# Rev_1.net
KiCad netlist of a schematic drawn in EAGLE
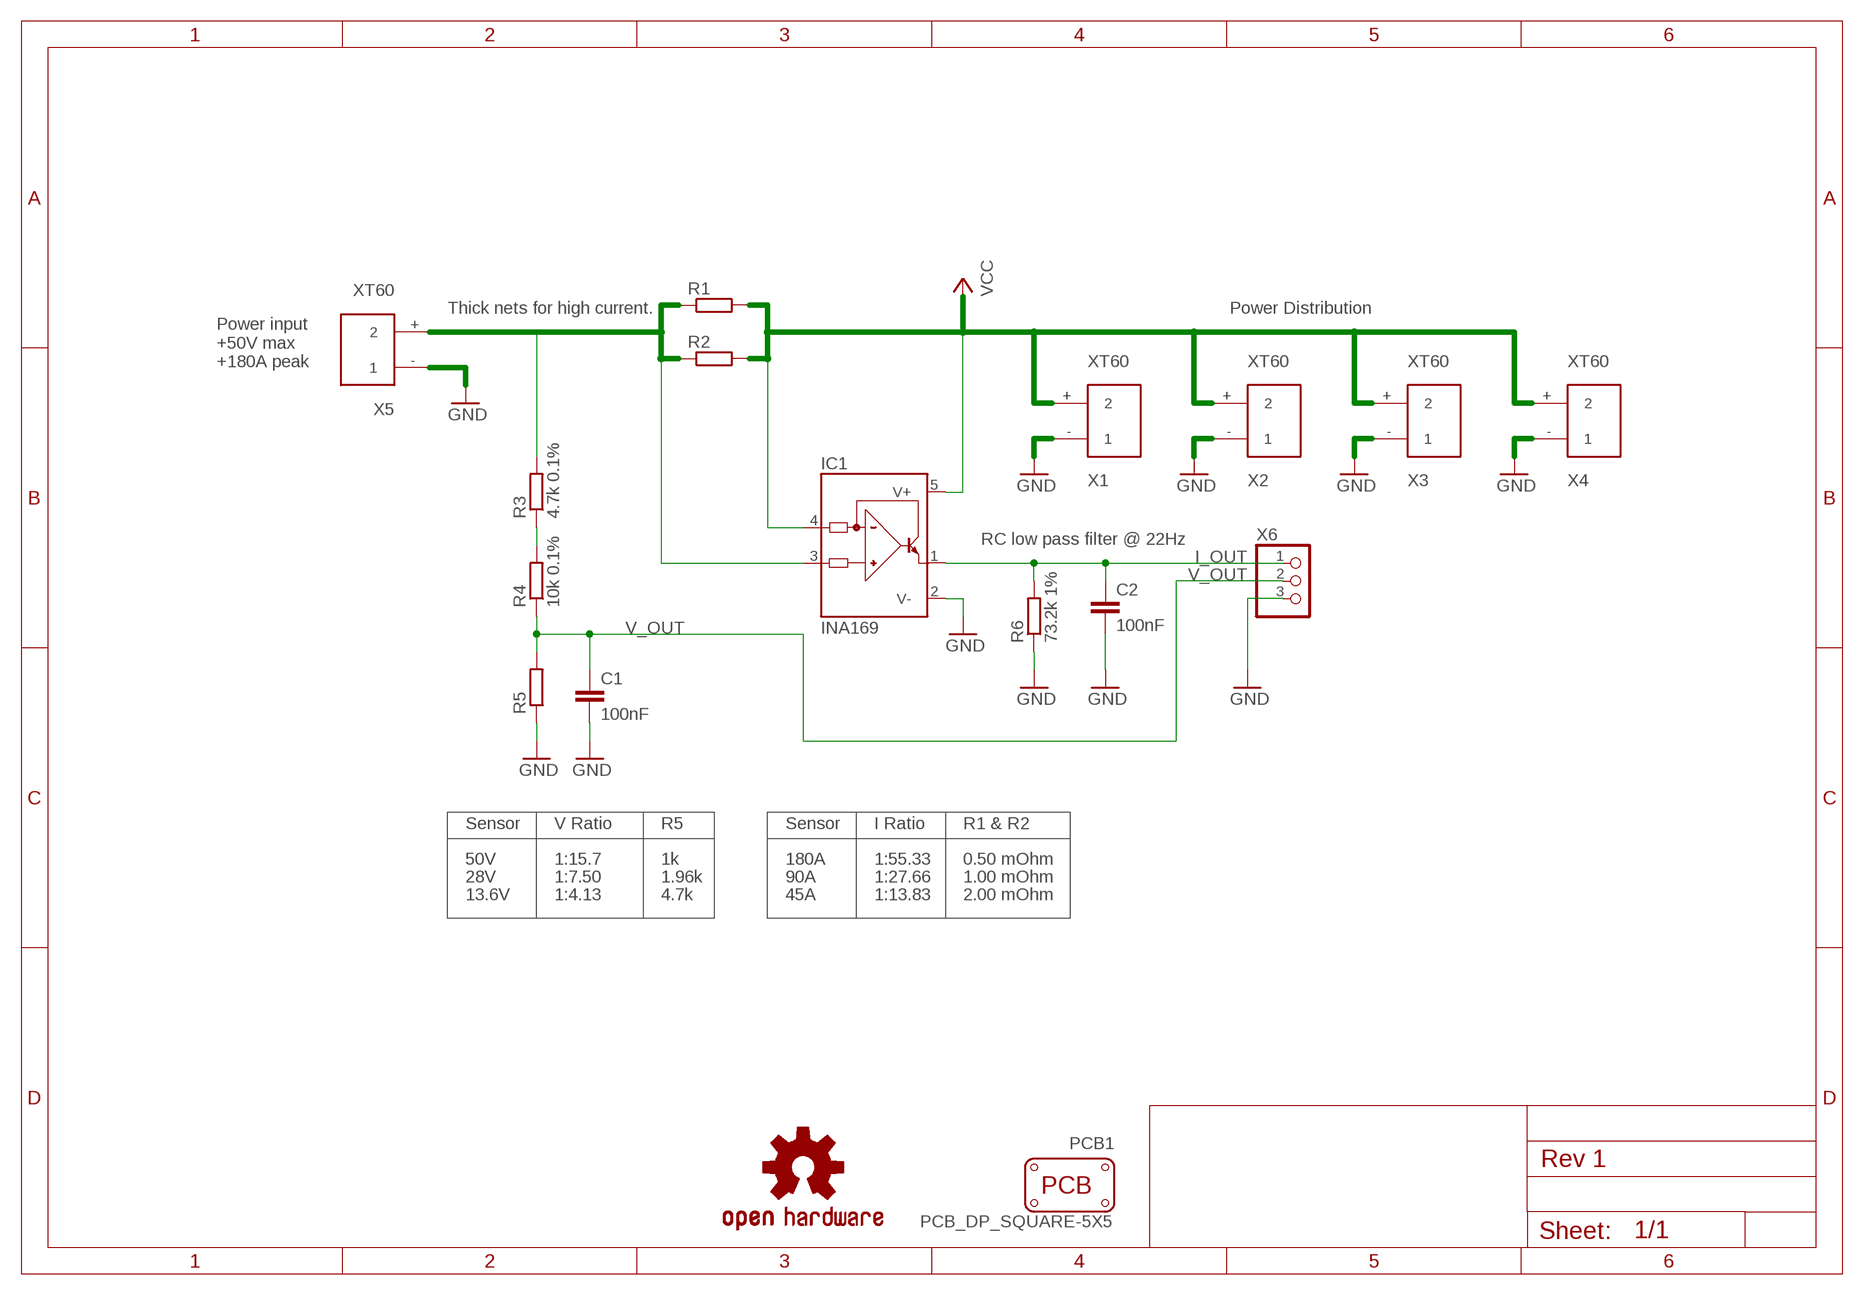
[diagram p0: schematic, sheet 1]

(export (version "E")
  (design (tool "Eeschema 10.0.6"))
  (components
    (comp (ref "C1")
      (value "100nF")
      (footprint "eagle-import:C0805")
      (fields (field (name "MF") "AVX") (field (name "MPN") "02016D104KAT2A"))
      (libsource (lib "eagle-import") (part "C-EUC0805"))
    )
    (comp (ref "C2")
      (value "100nF")
      (footprint "eagle-import:C0805")
      (fields (field (name "MF") "AVX") (field (name "MPN") "02016D104KAT2A"))
      (libsource (lib "eagle-import") (part "C-EUC0805"))
    )
    (comp (ref "IC1")
      (value "INA169")
      (footprint "eagle-import:SOT23-5")
      (fields (field (name "MF") "TEXAS INSTRUMENTS") (field (name "MPN") "INA169NA/250G4"))
      (libsource (lib "eagle-import") (part "INA168"))
    )
    (comp (ref "LOGO1")
      (value "OSHW-LOGOL")
      (footprint "eagle-import:OSHW-LOGO-L")
      (libsource (lib "eagle-import") (part "OSHW-LOGOL"))
    )
    (comp (ref "PCB1")
      (value "PCB_DP_SQUARE-5X5")
      (footprint "eagle-import:DP5050_V1")
      (libsource (lib "eagle-import") (part "PCB_DP_SQUARE-5X5"))
    )
    (comp (ref "R1")
      (value "R-EU_R2512")
      (footprint "eagle-import:R2512")
      (libsource (lib "eagle-import") (part "R-EU_R2512"))
    )
    (comp (ref "R2")
      (value "R-EU_R2512")
      (footprint "eagle-import:R2512")
      (libsource (lib "eagle-import") (part "R-EU_R2512"))
    )
    (comp (ref "R3")
      (value "4.7k 0.1%")
      (footprint "eagle-import:R0805")
      (fields (field (name "MF") "SUSUMU") (field (name "MPN") "RR1220P-472-B-T5"))
      (libsource (lib "eagle-import") (part "R-EU_R0805"))
    )
    (comp (ref "R4")
      (value "10k 0.1%")
      (footprint "eagle-import:R0805")
      (fields (field (name "MF") "SUSUMU") (field (name "MPN") "RR1220P-103-B-T5"))
      (libsource (lib "eagle-import") (part "R-EU_R0805"))
    )
    (comp (ref "R5")
      (value "R-EU_R0805")
      (footprint "eagle-import:R0805")
      (libsource (lib "eagle-import") (part "R-EU_R0805"))
    )
    (comp (ref "R6")
      (value "73.2k 1%")
      (footprint "eagle-import:R0805")
      (libsource (lib "eagle-import") (part "R-EU_R0805"))
    )
    (comp (ref "X1")
      (value "XT60")
      (footprint "eagle-import:XT60")
      (libsource (lib "eagle-import") (part "XT60"))
    )
    (comp (ref "X2")
      (value "XT60")
      (footprint "eagle-import:XT60")
      (libsource (lib "eagle-import") (part "XT60"))
    )
    (comp (ref "X3")
      (value "XT60")
      (footprint "eagle-import:XT60")
      (libsource (lib "eagle-import") (part "XT60"))
    )
    (comp (ref "X4")
      (value "XT60")
      (footprint "eagle-import:XT60")
      (libsource (lib "eagle-import") (part "XT60"))
    )
    (comp (ref "X5")
      (value "XT60")
      (footprint "eagle-import:XT60")
      (libsource (lib "eagle-import") (part "XT60"))
    )
    (comp (ref "X6")
      (value "PINHD-1X3")
      (footprint "eagle-import:1X03")
      (libsource (lib "eagle-import") (part "PINHD-1X3"))
    )
  )
  (nets
    (net (code "1") (name "/I_OUT") (class "Default")
      (node (ref "C2") (pin "1") (pinfunction "1_1") (pintype "passive"))
      (node (ref "IC1") (pin "1") (pinfunction "OUT_1") (pintype "output"))
      (node (ref "R6") (pin "2") (pinfunction "2_2") (pintype "passive"))
      (node (ref "X6") (pin "1") (pinfunction "1_1") (pintype "passive"))
    )
    (net (code "2") (name "/V_OUT") (class "Default")
      (node (ref "C1") (pin "1") (pinfunction "1_1") (pintype "passive"))
      (node (ref "R4") (pin "1") (pinfunction "1_1") (pintype "passive"))
      (node (ref "R5") (pin "2") (pinfunction "2_2") (pintype "passive"))
      (node (ref "X6") (pin "2") (pinfunction "2_2") (pintype "passive"))
    )
    (net (code "3") (name "GND") (class "Default")
      (node (ref "C1") (pin "2") (pinfunction "2_2") (pintype "passive"))
      (node (ref "C2") (pin "2") (pinfunction "2_2") (pintype "passive"))
      (node (ref "IC1") (pin "2") (pinfunction "V-_2") (pintype "power_in"))
      (node (ref "R5") (pin "1") (pinfunction "1_1") (pintype "passive"))
      (node (ref "R6") (pin "1") (pinfunction "1_1") (pintype "passive"))
      (node (ref "X1") (pin "-") (pinfunction "1_-") (pintype "bidirectional"))
      (node (ref "X2") (pin "-") (pinfunction "1_-") (pintype "bidirectional"))
      (node (ref "X3") (pin "-") (pinfunction "1_-") (pintype "bidirectional"))
      (node (ref "X4") (pin "-") (pinfunction "1_-") (pintype "bidirectional"))
      (node (ref "X5") (pin "-") (pinfunction "1_-") (pintype "bidirectional"))
      (node (ref "X6") (pin "3") (pinfunction "3_3") (pintype "passive"))
    )
    (net (code "4") (name "Net-(IC1-IN+)") (class "Default")
      (node (ref "IC1") (pin "3") (pinfunction "IN+_3") (pintype "input"))
      (node (ref "R1") (pin "1") (pinfunction "1_1") (pintype "passive"))
      (node (ref "R2") (pin "1") (pinfunction "1_1") (pintype "passive"))
      (node (ref "R3") (pin "2") (pinfunction "2_2") (pintype "passive"))
      (node (ref "X5") (pin "+") (pinfunction "2_+") (pintype "bidirectional"))
    )
    (net (code "5") (name "Net-(R3-Pad1)") (class "Default")
      (node (ref "R3") (pin "1") (pinfunction "1_1") (pintype "passive"))
      (node (ref "R4") (pin "2") (pinfunction "2_2") (pintype "passive"))
    )
    (net (code "6") (name "VCC") (class "Default")
      (node (ref "IC1") (pin "4") (pinfunction "IN-_4") (pintype "input"))
      (node (ref "IC1") (pin "5") (pinfunction "V+_5") (pintype "power_in"))
      (node (ref "R1") (pin "2") (pinfunction "2_2") (pintype "passive"))
      (node (ref "R2") (pin "2") (pinfunction "2_2") (pintype "passive"))
      (node (ref "X1") (pin "+") (pinfunction "2_+") (pintype "bidirectional"))
      (node (ref "X2") (pin "+") (pinfunction "2_+") (pintype "bidirectional"))
      (node (ref "X3") (pin "+") (pinfunction "2_+") (pintype "bidirectional"))
      (node (ref "X4") (pin "+") (pinfunction "2_+") (pintype "bidirectional"))
    )
  )
)
